# Reverse_Protection.net
KiCad netlist of a schematic drawn in Altium Designer
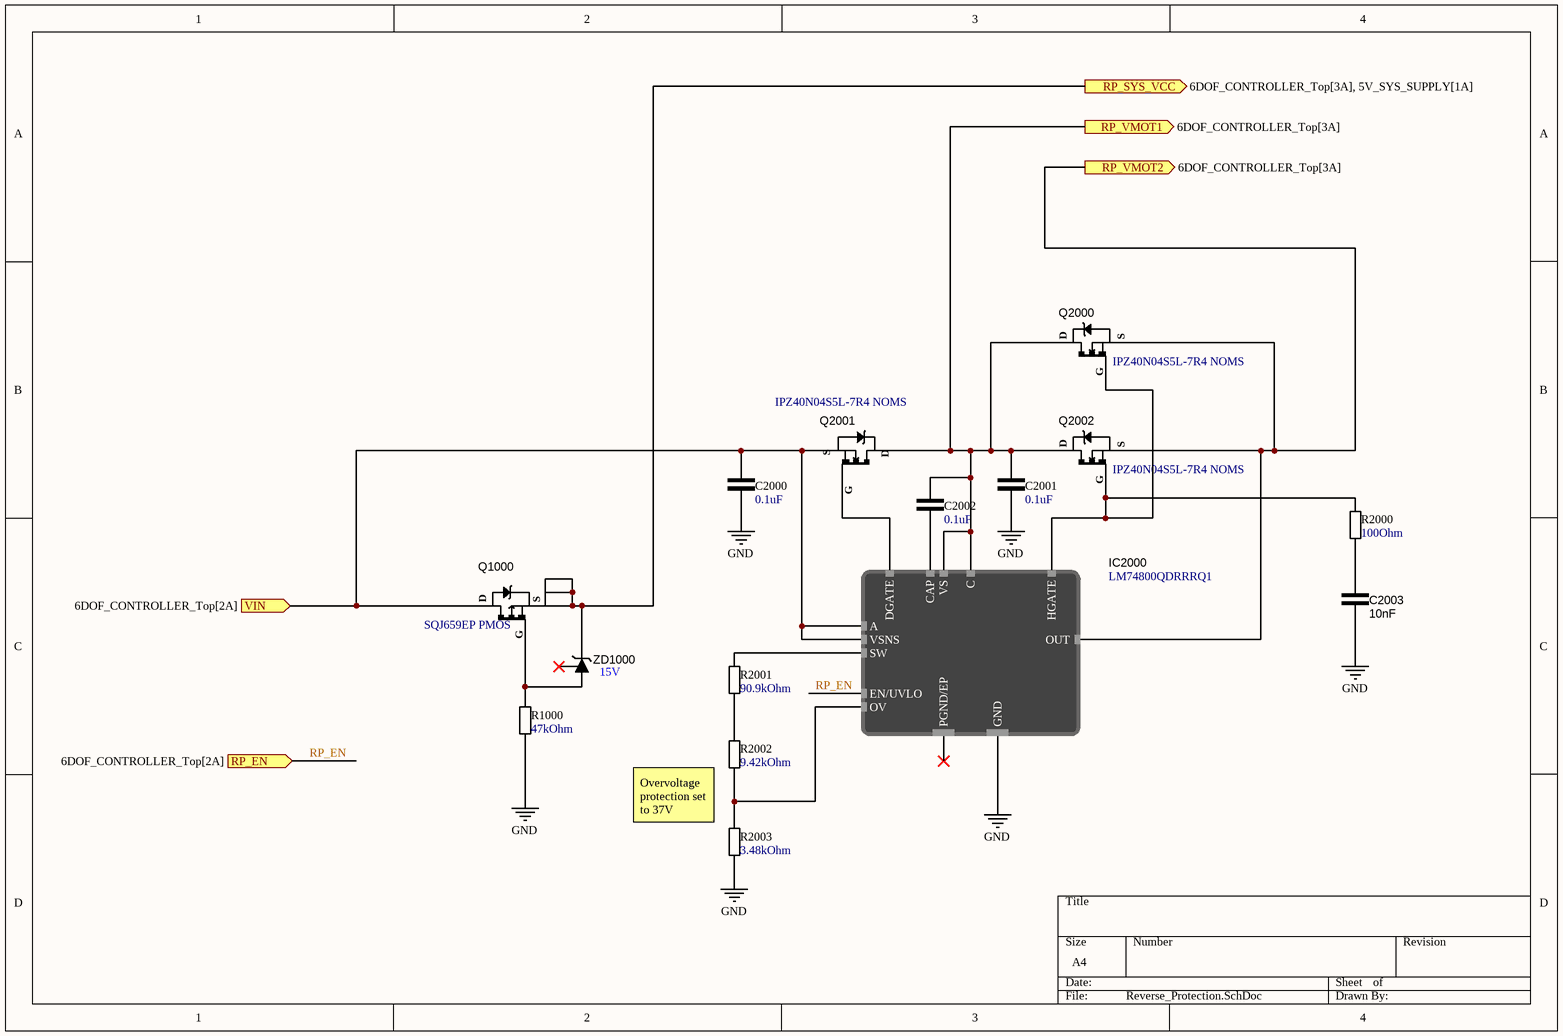
[diagram p0: Reverse_Protection.SchDoc]

(export (version "E")
  (design (tool "Eeschema 10.0.6"))
  (components
    (comp (ref "C2000")
      (value "0.1uF")
      (footprint "CAP_0603")
      (description "0.1 µF ±10% 50V Ceramic Capacitor X7R 0603 (1608 Metric)")
      (fields (field (name "DIGIKEY PART NUMBER") "1276-1000-1-ND"))
      (libsource (lib "CapacitorsIntegrated") (part "C000018"))
    )
    (comp (ref "C2001")
      (value "0.1uF")
      (footprint "CAP_0603")
      (description "0.1 µF ±10% 50V Ceramic Capacitor X7R 0603 (1608 Metric)")
      (fields (field (name "DIGIKEY PART NUMBER") "1276-1000-1-ND"))
      (libsource (lib "CapacitorsIntegrated") (part "C000018"))
    )
    (comp (ref "C2002")
      (value "0.1uF")
      (footprint "CAP_0603")
      (description "0.1 µF ±10% 50V Ceramic Capacitor X7R 0603 (1608 Metric)")
      (fields (field (name "DIGIKEY PART NUMBER") "1276-1000-1-ND"))
      (libsource (lib "CapacitorsIntegrated") (part "C000018"))
    )
    (comp (ref "C2003")
      (value "10nF")
      (footprint "CAP_0603")
      (description "10000 pF ±10% 50V Ceramic Capacitor X7R 0603 (1608 Metric)")
      (fields (field (name "DIGIKEY PART NUMBER") "399-C0603C103K5RACTUCT-ND"))
      (libsource (lib "CapacitorsIntegrated") (part "C000034"))
    )
    (comp (ref "IC2000")
      (value "LM74800QDRRRQ1")
      (footprint "SON50P300X80_HS-13N")
      (description "OR Controller N+1 ORing Controller N-Channel 1:1 12-WSON (3x3)")
      (fields
        (field (name "DIGIKEY PART NUMBER") "296-LM74800QDRRRQ1CT-ND")
        (field (name "MOUSER PART NUMBER") "595-LM74800QDRRRQ1")
      )
      (libsource (lib "IntegratedCircuits") (part "LM74800QDRRRQ1"))
    )
    (comp (ref "Q1000")
      (value "SQJ659EP PMOS")
      (footprint "PowerPAK SO-8L SINGLE")
      (description "P-Channel 60 V 52A (Tc) 83W (Tc) Surface Mount PowerPAK® SO-8")
      (fields
        (field (name "DIGIKEY PART NUMBER") "SQJ459EP-T1_GE3CT-ND")
        (field (name "MOUSER PART NUMBER") "78-SQJ459EP-T2_BE3")
      )
      (libsource (lib "Miscellaneous_Lib1") (part "00000005"))
    )
    (comp (ref "Q2000")
      (value "IPZ40N04S5L-7R4 NOMS")
      (footprint "PG-TSDSON-8-32")
      (description "N-Channel 40 V 40A (Tc) 34W (Tc) Surface Mount PG-TSDSON-8")
      (fields
        (field (name "DIGIKEY PART NUMBER") "IPZ40N04S5L7R4ATMA1CT-ND")
        (field (name "MOUSER PART NUMBER") "726-IPZ40N04S5L7R4AT")
      )
      (libsource (lib "Miscellaneous_Lib1") (part "00000007"))
    )
    (comp (ref "Q2001")
      (value "IPZ40N04S5L-7R4 NOMS")
      (footprint "PG-TSDSON-8-32")
      (description "N-Channel 40 V 40A (Tc) 34W (Tc) Surface Mount PG-TSDSON-8")
      (fields
        (field (name "DIGIKEY PART NUMBER") "IPZ40N04S5L7R4ATMA1CT-ND")
        (field (name "MOUSER PART NUMBER") "726-IPZ40N04S5L7R4AT")
      )
      (libsource (lib "") (part "00000007_1"))
    )
    (comp (ref "Q2002")
      (value "IPZ40N04S5L-7R4 NOMS")
      (footprint "PG-TSDSON-8-32")
      (description "N-Channel 40 V 40A (Tc) 34W (Tc) Surface Mount PG-TSDSON-8")
      (fields
        (field (name "DIGIKEY PART NUMBER") "IPZ40N04S5L7R4ATMA1CT-ND")
        (field (name "MOUSER PART NUMBER") "726-IPZ40N04S5L7R4AT")
      )
      (libsource (lib "Miscellaneous_Lib1") (part "00000007"))
    )
    (comp (ref "R1000")
      (value "47kOhm")
      (footprint "RES_0603")
      (description "47 kOhms ±1% 0.1W, 1/10W Chip Resistor 0603 (1608 Metric) Moisture Resistant Thick Film")
      (fields (field (name "DIGIKEY PART NUMBER") "311-47.0KHRCT-ND"))
      (libsource (lib "ResistorsIntegrated") (part "R000010"))
    )
    (comp (ref "R2000")
      (value "100Ohm")
      (footprint "RES_0603")
      (description "100 Ohms ±1% 0.1W, 1/10W Chip Resistor 0603 (1608 Metric) Moisture Resistant Thick Film")
      (fields (field (name "DIGIKEY PART NUMBER") "311-100HRCT-ND"))
      (libsource (lib "ResistorsIntegrated") (part "R000030"))
    )
    (comp (ref "R2001")
      (value "90.9kOhm")
      (footprint "RES_0603")
      (description "90.9 kOhms ±1% 0.1W, 1/10W Chip Resistor 0603 (1608 Metric) Automotive AEC-Q200 Thick Film")
      (fields (field (name "DIGIKEY PART NUMBER") "P90.9KHCT-ND"))
      (libsource (lib "ResistorsIntegrated") (part "R000027"))
    )
    (comp (ref "R2002")
      (value "9.42kOhm")
      (footprint "RES_0603")
      (fields (field (name "DIGIKEY PART NUMBER") "2019-RN73H1JTTD9421F25CT-ND"))
      (libsource (lib "ResistorsIntegrated") (part "R000028"))
    )
    (comp (ref "R2003")
      (value "3.48kOhm")
      (footprint "RES_0603")
      (description "3.48 kOhms ±1% 0.1W, 1/10W Chip Resistor 0603 (1608 Metric) Automotive AEC-Q200 Thick Film")
      (fields (field (name "DIGIKEY PART NUMBER") "RMCF0603FT3K48CT-ND"))
      (libsource (lib "ResistorsIntegrated") (part "R000029"))
    )
    (comp (ref "ZD1000")
      (value "DZ23C15-E3-08 Zener Diode")
      (footprint "SOT95P245X96-3N")
      (description "Zener Diode Array 1 Pair Common Cathode 15 V 300 mW ±5% SOT-23-3")
      (fields (field (name "DIGIKEY PART NUMBER") "112-DZ23C15-E3-08CT-ND"))
      (libsource (lib "Miscellaneous_Lib1") (part "00000006"))
    )
  )
  (nets
    (net (code "1") (name "/RP_EN") (class "Default")
      (node (ref "IC2000") (pin "6") (pinfunction "EN/UVLO_6") (pintype "passive"))
    )
    (net (code "2") (name "/RP_SYS_VCC") (class "Default")
      (node (ref "Q1000") (pin "S") (pinfunction "S1_S") (pintype "passive"))
      (node (ref "ZD1000") (pin "3") (pinfunction "Cathode_3") (pintype "passive"))
    )
    (net (code "3") (name "/RP_VMOT1") (class "Default")
      (node (ref "C2001") (pin "2") (pinfunction "2_2") (pintype "passive"))
      (node (ref "C2002") (pin "2") (pinfunction "2_2") (pintype "passive"))
      (node (ref "IC2000") (pin "10") (pinfunction "VS_10") (pintype "passive"))
      (node (ref "IC2000") (pin "12") (pinfunction "C_12") (pintype "passive"))
      (node (ref "Q2000") (pin "D") (pinfunction "Drain_D") (pintype "passive"))
      (node (ref "Q2001") (pin "D") (pinfunction "Drain_D") (pintype "passive"))
      (node (ref "Q2002") (pin "D") (pinfunction "Drain_D") (pintype "passive"))
    )
    (net (code "4") (name "/RP_VMOT2") (class "Default")
      (node (ref "IC2000") (pin "9") (pinfunction "OUT_9") (pintype "passive"))
      (node (ref "Q2000") (pin "S") (pinfunction "Source_S") (pintype "passive"))
      (node (ref "Q2002") (pin "S") (pinfunction "Source_S") (pintype "passive"))
    )
    (net (code "5") (name "/VIN") (class "Default")
      (node (ref "C2000") (pin "2") (pinfunction "2_2") (pintype "passive"))
      (node (ref "IC2000") (pin "2") (pinfunction "A_2") (pintype "passive"))
      (node (ref "IC2000") (pin "3") (pinfunction "VSNS_3") (pintype "passive"))
      (node (ref "Q1000") (pin "D") (pinfunction "D_D") (pintype "passive"))
      (node (ref "Q2001") (pin "S") (pinfunction "Source_S") (pintype "passive"))
    )
    (net (code "6") (name "GND") (class "Default")
      (node (ref "C2000") (pin "1") (pinfunction "1_1") (pintype "passive"))
      (node (ref "C2001") (pin "1") (pinfunction "1_1") (pintype "passive"))
      (node (ref "C2003") (pin "1") (pinfunction "1_1") (pintype "passive"))
      (node (ref "IC2000") (pin "7") (pinfunction "GND_7") (pintype "passive"))
      (node (ref "R1000") (pin "1") (pinfunction "1_1") (pintype "passive"))
      (node (ref "R2003") (pin "1") (pinfunction "1_1") (pintype "passive"))
    )
    (net (code "7") (name "Net-(C2003-Pad2)") (class "Default")
      (node (ref "C2003") (pin "2") (pinfunction "2_2") (pintype "passive"))
      (node (ref "R2000") (pin "1") (pinfunction "1_1") (pintype "passive"))
    )
    (net (code "8") (name "Net-(IC2000-CAP)") (class "Default")
      (node (ref "C2002") (pin "1") (pinfunction "1_1") (pintype "passive"))
      (node (ref "IC2000") (pin "11") (pinfunction "CAP_11") (pintype "passive"))
    )
    (net (code "9") (name "Net-(IC2000-DGATE)") (class "Default")
      (node (ref "IC2000") (pin "1") (pinfunction "DGATE_1") (pintype "passive"))
      (node (ref "Q2001") (pin "G") (pinfunction "Gate_G") (pintype "passive"))
    )
    (net (code "10") (name "Net-(IC2000-HGATE)") (class "Default")
      (node (ref "IC2000") (pin "8") (pinfunction "HGATE_8") (pintype "passive"))
      (node (ref "Q2000") (pin "G") (pinfunction "Gate_G") (pintype "passive"))
      (node (ref "Q2002") (pin "G") (pinfunction "Gate_G") (pintype "passive"))
      (node (ref "R2000") (pin "2") (pinfunction "2_2") (pintype "passive"))
    )
    (net (code "11") (name "Net-(IC2000-OV)") (class "Default")
      (node (ref "IC2000") (pin "5") (pinfunction "OV_5") (pintype "passive"))
      (node (ref "R2002") (pin "1") (pinfunction "1_1") (pintype "passive"))
      (node (ref "R2003") (pin "2") (pinfunction "2_2") (pintype "passive"))
    )
    (net (code "12") (name "Net-(IC2000-SW)") (class "Default")
      (node (ref "IC2000") (pin "4") (pinfunction "SW_4") (pintype "passive"))
      (node (ref "R2001") (pin "2") (pinfunction "2_2") (pintype "passive"))
    )
    (net (code "13") (name "Net-(Q1000-PadG)") (class "Default")
      (node (ref "Q1000") (pin "G") (pinfunction "G_G") (pintype "passive"))
      (node (ref "R1000") (pin "2") (pinfunction "2_2") (pintype "passive"))
      (node (ref "ZD1000") (pin "1") (pinfunction "Anode_1") (pintype "passive"))
    )
    (net (code "14") (name "Net-(R2001-Pad1)") (class "Default")
      (node (ref "R2001") (pin "1") (pinfunction "1_1") (pintype "passive"))
      (node (ref "R2002") (pin "2") (pinfunction "2_2") (pintype "passive"))
    )
    (net (code "15") (name "unconnected-(IC2000-PGND{slash}EP-Pad13)") (class "Default")
      (node (ref "IC2000") (pin "13") (pinfunction "PGND/EP_13") (pintype "passive+no_connect"))
    )
    (net (code "16") (name "unconnected-(ZD1000-Anode-Pad2)") (class "Default")
      (node (ref "ZD1000") (pin "2") (pinfunction "Anode_2") (pintype "passive+no_connect"))
    )
  )
)
